# MEMSBreakout.net
KiCad netlist of a schematic drawn in Altium Designer
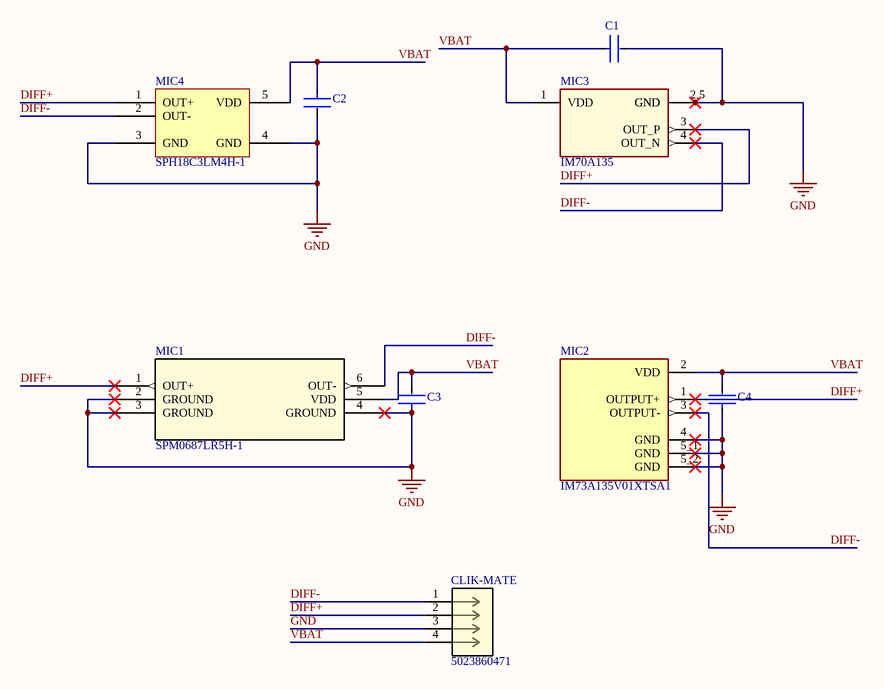
[diagram p0: MEMSBreakout.SchDoc]

(export (version "E")
  (design (tool "Eeschema 10.0.6"))
  (components
    (comp (ref "C1")
      (value "C1206C104J3GACTU")
      (footprint "FP-C1206C-EB-MFG")
      (description "CAP CER 0.1UF 25V 5% NP0 1206")
      (fields
        (field (name "TOLERANCE") "0.05")
        (field (name "OCTOPART") "https://octopart.com/c1206c104j3gactu-kemet-9145095")
      )
      (libsource (lib "Altium Content Vault") (part "b4654b650e69147ec39a6b967a45e02"))
    )
    (comp (ref "C2")
      (value "C1206C104J3GACTU")
      (footprint "FP-C1206C-EB-MFG")
      (description "CAP CER 0.1UF 25V 5% NP0 1206")
      (fields
        (field (name "TOLERANCE") "0.05")
        (field (name "OCTOPART") "https://octopart.com/c1206c104j3gactu-kemet-9145095")
      )
      (libsource (lib "Altium Content Vault") (part "b4654b650e69147ec39a6b967a45e02"))
    )
    (comp (ref "C3")
      (value "C1206C104J3GACTU")
      (footprint "FP-C1206C-EB-MFG")
      (description "CAP CER 0.1UF 25V 5% NP0 1206")
      (fields
        (field (name "TOLERANCE") "0.05")
        (field (name "OCTOPART") "https://octopart.com/c1206c104j3gactu-kemet-9145095")
      )
      (libsource (lib "Altium Content Vault") (part "b4654b650e69147ec39a6b967a45e02"))
    )
    (comp (ref "C4")
      (value "C1206C104J3GACTU")
      (footprint "FP-C1206C-EB-MFG")
      (description "CAP CER 0.1UF 25V 5% NP0 1206")
      (fields
        (field (name "TOLERANCE") "0.05")
        (field (name "OCTOPART") "https://octopart.com/c1206c104j3gactu-kemet-9145095")
      )
      (libsource (lib "Altium Content Vault") (part "b4654b650e69147ec39a6b967a45e02"))
    )
    (comp (ref "CLIK-MATE")
      (value "5023860471")
      (footprint "CONN_502386-04xx_MOL")
      (description "No Description Available")
      (libsource (lib "5023860471") (part "5023860471"))
    )
    (comp (ref "MIC1")
      (value "SPM0687LR5H-1")
      (footprint "SPM0687LR5H-1_KNO")
      (description "No Description Available")
      (libsource (lib "SPM0687LR5H-1") (part "SPM0687LR5H-1"))
    )
    (comp (ref "MIC2")
      (value "IM73A135V01XTSA1")
      (footprint "MIC_IM73A135V01XTSA1")
      (fields (field (name "MF") "Infineon Technologies"))
      (libsource (lib "IM73A135V01XTSA1") (part "IM73A135V01XTSA1"))
    )
    (comp (ref "MIC3")
      (value "IM70A135")
      (footprint "IFX-PG-TLGA-5-2-V")
      (description "High Performance Analog XENSIV MEMS Microphone")
      (fields (field (name "MANUFACTURER") "Infineon Technologies"))
      (libsource (lib "IM70A135V01XTMA1") (part "IM70A135"))
    )
    (comp (ref "MIC4")
      (value "SPH18C3LM4H-1")
      (footprint "SPH18C3LM4H-1")
      (libsource (lib "SPH18C3LM4H-1") (part "SPH18C3LM4H-1"))
    )
  )
  (nets
    (net (code "1") (name "/DIFF+") (class "Default")
      (node (ref "CLIK-MATE") (pin "2") (pinfunction "2_2") (pintype "passive"))
      (node (ref "MIC1") (pin "1") (pinfunction "OUT+_1") (pintype "output"))
      (node (ref "MIC2") (pin "1") (pinfunction "OUTPUT+_1") (pintype "output"))
      (node (ref "MIC3") (pin "3") (pinfunction "OUT_P_3") (pintype "output"))
      (node (ref "MIC4") (pin "1") (pinfunction "OUT+_1") (pintype "passive"))
    )
    (net (code "2") (name "/DIFF-") (class "Default")
      (node (ref "CLIK-MATE") (pin "1") (pinfunction "1_1") (pintype "passive"))
      (node (ref "MIC1") (pin "6") (pinfunction "OUT-_6") (pintype "output"))
      (node (ref "MIC2") (pin "3") (pinfunction "OUTPUT-_3") (pintype "output"))
      (node (ref "MIC3") (pin "4") (pinfunction "OUT_N_4") (pintype "output"))
      (node (ref "MIC4") (pin "2") (pinfunction "OUT-_2") (pintype "passive"))
    )
    (net (code "3") (name "/VBAT") (class "Default")
      (node (ref "C1") (pin "1") (pinfunction "1_1") (pintype "passive"))
      (node (ref "C2") (pin "1") (pinfunction "1_1") (pintype "passive"))
      (node (ref "C3") (pin "2") (pinfunction "2_2") (pintype "passive"))
      (node (ref "C4") (pin "2") (pinfunction "2_2") (pintype "passive"))
      (node (ref "CLIK-MATE") (pin "4") (pinfunction "4_4") (pintype "passive"))
      (node (ref "MIC1") (pin "5") (pinfunction "VDD_5") (pintype "power_in"))
      (node (ref "MIC2") (pin "2") (pinfunction "VDD_2") (pintype "power_in"))
      (node (ref "MIC3") (pin "1") (pinfunction "VDD_1") (pintype "power_in"))
      (node (ref "MIC4") (pin "5") (pinfunction "VDD_5") (pintype "passive"))
    )
    (net (code "4") (name "GND") (class "Default")
      (node (ref "C1") (pin "2") (pinfunction "2_2") (pintype "passive"))
      (node (ref "C2") (pin "2") (pinfunction "2_2") (pintype "passive"))
      (node (ref "C3") (pin "1") (pinfunction "1_1") (pintype "passive"))
      (node (ref "C4") (pin "1") (pinfunction "1_1") (pintype "passive"))
      (node (ref "CLIK-MATE") (pin "3") (pinfunction "3_3") (pintype "passive"))
      (node (ref "MIC1") (pin "2") (pinfunction "GROUND_2") (pintype "power_in"))
      (node (ref "MIC1") (pin "3") (pinfunction "GROUND_3") (pintype "power_in"))
      (node (ref "MIC1") (pin "4") (pinfunction "GROUND_4") (pintype "power_in"))
      (node (ref "MIC2") (pin "4") (pinfunction "GND_4") (pintype "power_in"))
      (node (ref "MIC2") (pin "5_1") (pinfunction "GND_5_1") (pintype "power_in"))
      (node (ref "MIC2") (pin "5_2") (pinfunction "GND_5_2") (pintype "power_in"))
      (node (ref "MIC3") (pin "2") (pinfunction "GND_2") (pintype "power_in"))
      (node (ref "MIC3") (pin "5") (pinfunction "GND_5") (pintype "power_in"))
      (node (ref "MIC4") (pin "3") (pinfunction "GND_3") (pintype "passive"))
      (node (ref "MIC4") (pin "4") (pinfunction "GND_4") (pintype "passive"))
    )
  )
)
